# jtag.net
KiCad netlist of a schematic drawn in Altium Designer
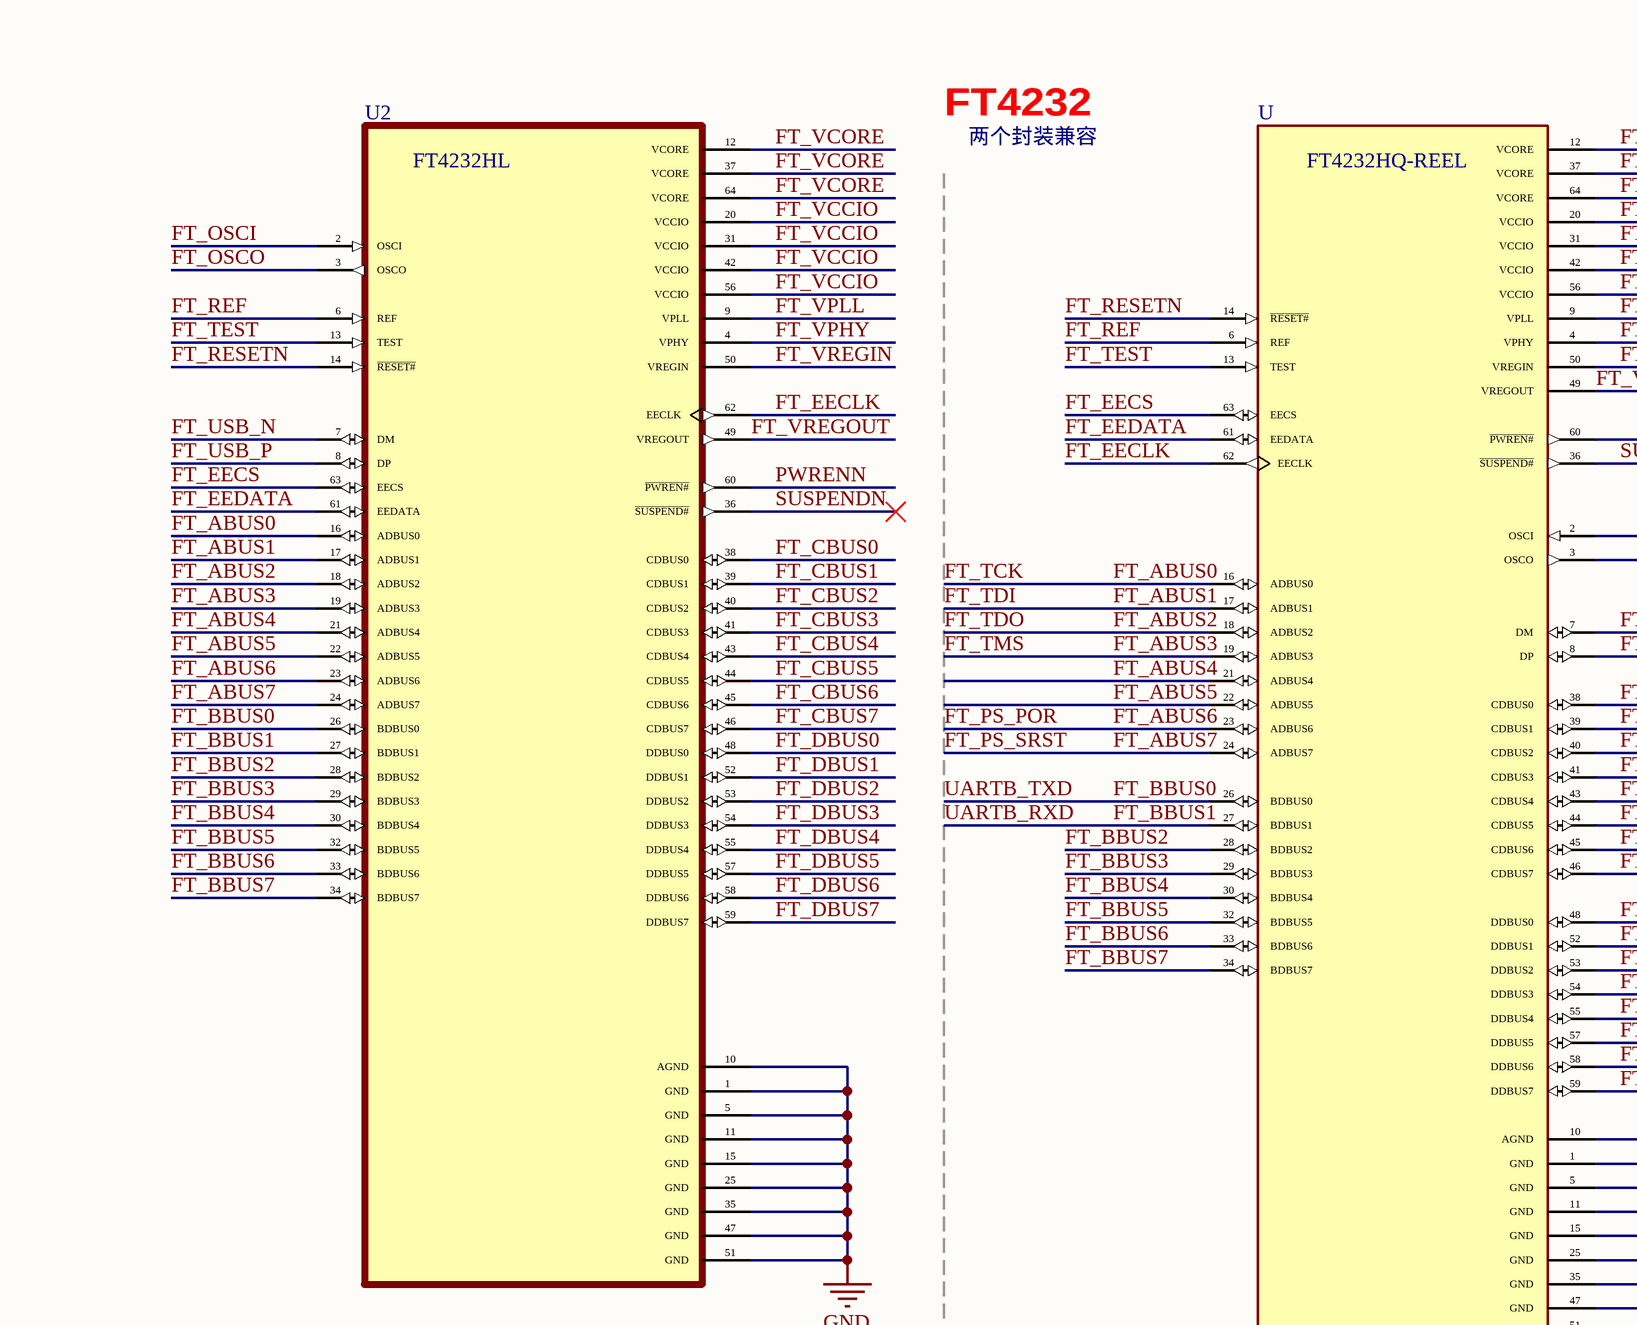
[diagram p0: jtag.schdoc, top left]
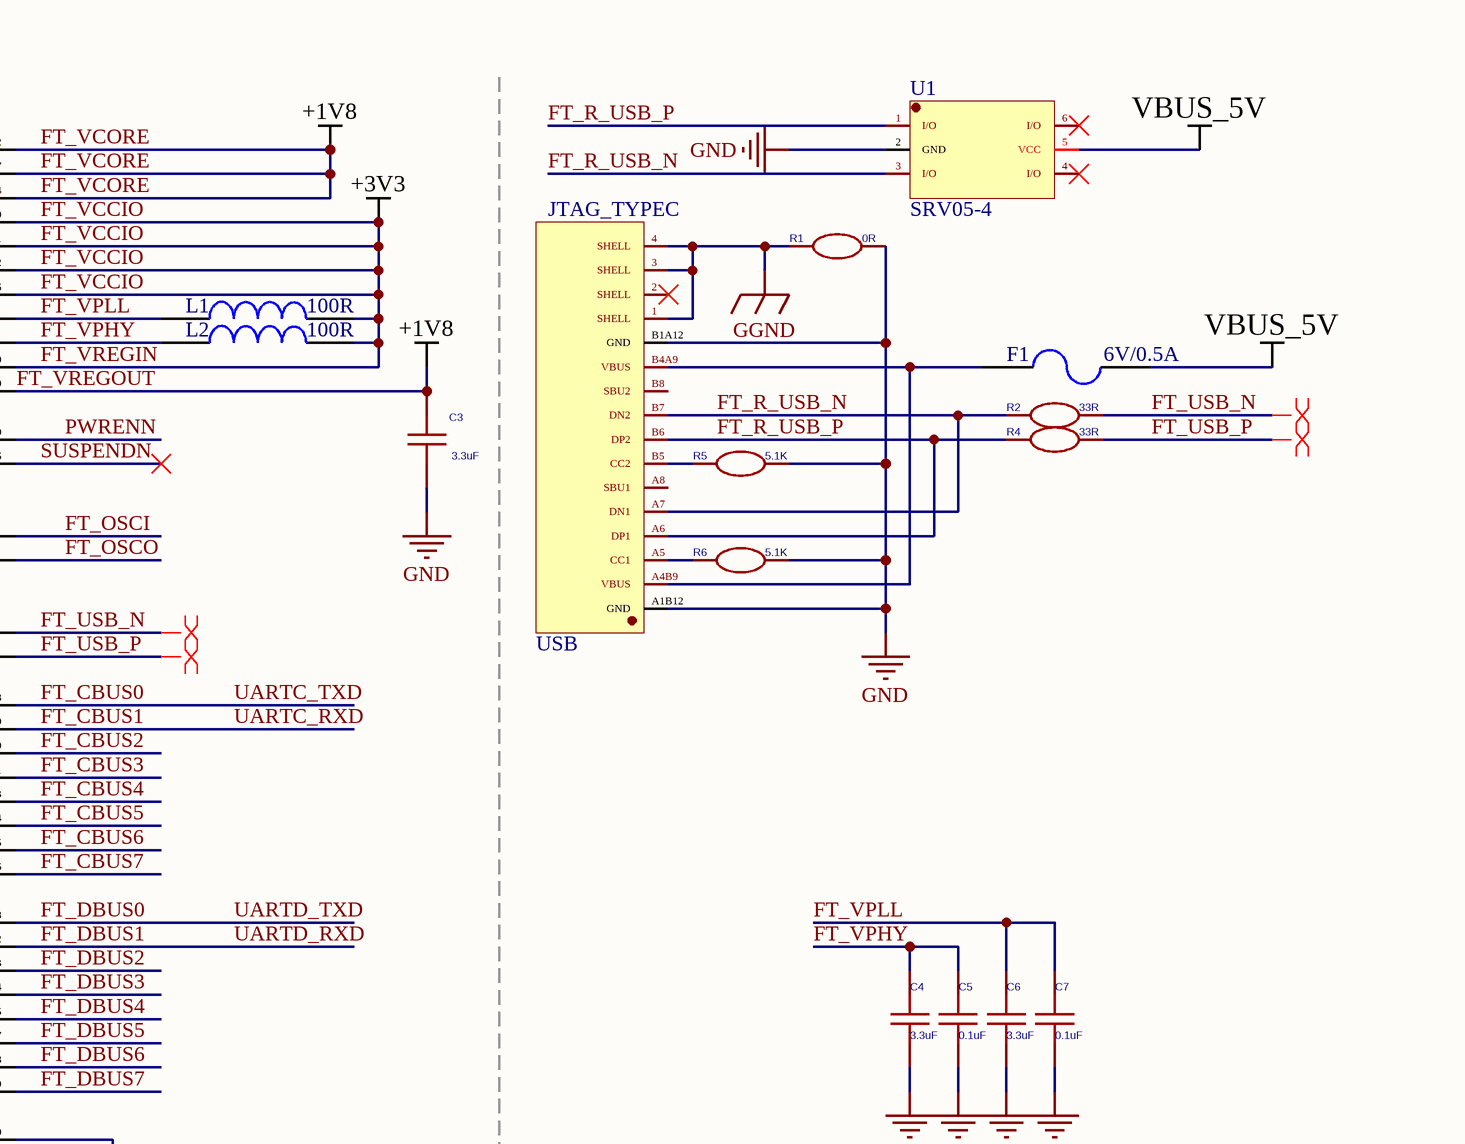
[diagram p1: jtag.schdoc, top right]
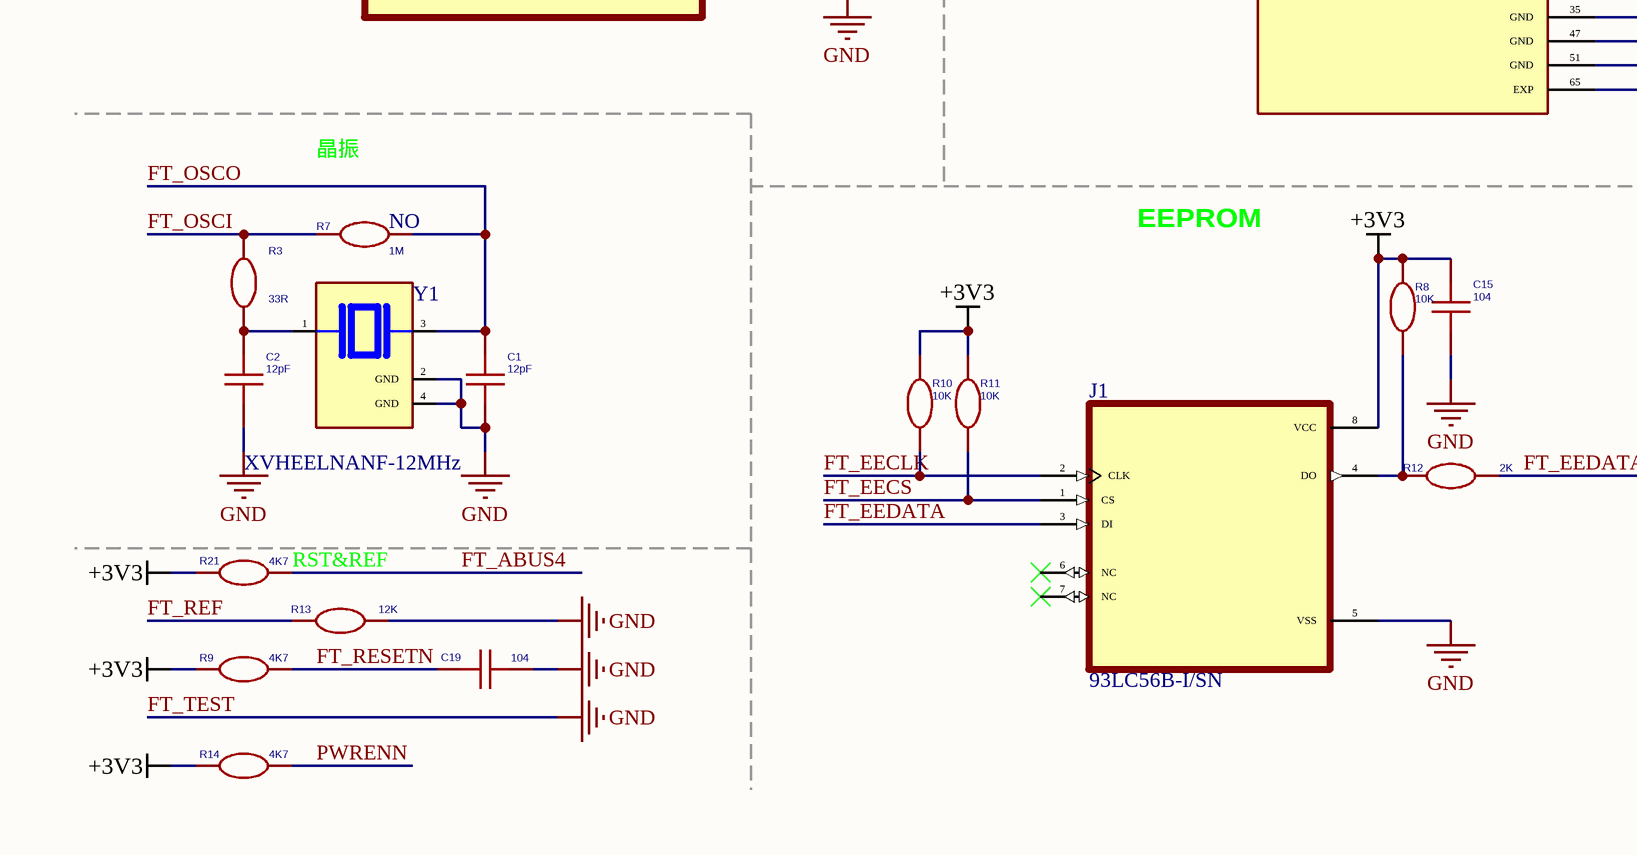
[diagram p2: jtag.schdoc, bottom left]
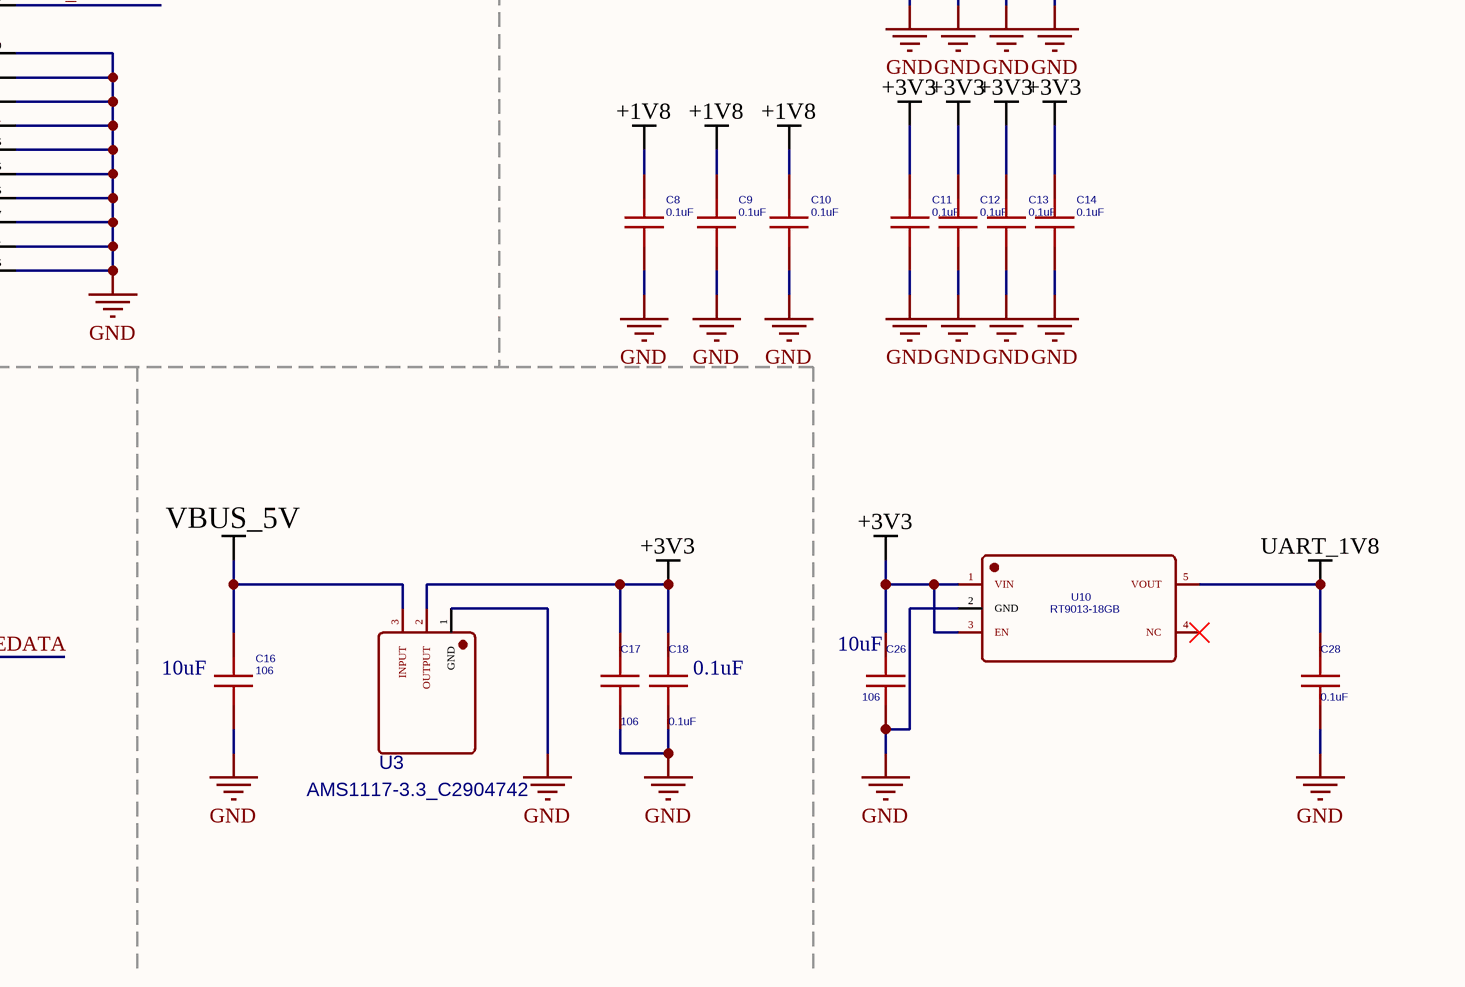
[diagram p3: jtag.schdoc, bottom right]

(export (version "E")
  (design (tool "Eeschema 10.0.6"))
  (components
    (comp (ref "C1")
      (value "12pF")
      (footprint "0603C")
      (fields (field (name "CONTRIBUTOR") "LCEDA_Lib"))
      (libsource (lib "altium-import") (part "root_3_12pF_"))
    )
    (comp (ref "C2")
      (value "12pF")
      (footprint "0603C")
      (fields (field (name "CONTRIBUTOR") "LCEDA_Lib"))
      (libsource (lib "altium-import") (part "root_3_12pF_"))
    )
    (comp (ref "C3")
      (value "3.3uF")
      (footprint "0603C")
      (fields (field (name "CONTRIBUTOR") "LCEDA_Lib"))
      (libsource (lib "altium-import") (part "root_1_104_"))
    )
    (comp (ref "C4")
      (value "3.3uF")
      (footprint "0603C")
      (fields (field (name "CONTRIBUTOR") "LCEDA_Lib"))
      (libsource (lib "altium-import") (part "root_1_104_"))
    )
    (comp (ref "C5")
      (value "0.1uF")
      (footprint "0603C")
      (fields (field (name "CONTRIBUTOR") "LCEDA_Lib"))
      (libsource (lib "altium-import") (part "root_1_104_"))
    )
    (comp (ref "C6")
      (value "3.3uF")
      (footprint "0603C")
      (fields (field (name "CONTRIBUTOR") "LCEDA_Lib"))
      (libsource (lib "altium-import") (part "root_1_104_"))
    )
    (comp (ref "C7")
      (value "0.1uF")
      (footprint "0603C")
      (fields (field (name "CONTRIBUTOR") "LCEDA_Lib"))
      (libsource (lib "altium-import") (part "root_1_104_"))
    )
    (comp (ref "C8")
      (value "0.1uF")
      (footprint "0603C")
      (fields (field (name "CONTRIBUTOR") "LCEDA_Lib"))
      (libsource (lib "altium-import") (part "root_1_104_"))
    )
    (comp (ref "C9")
      (value "0.1uF")
      (footprint "0603C")
      (fields (field (name "CONTRIBUTOR") "LCEDA_Lib"))
      (libsource (lib "altium-import") (part "root_1_104_"))
    )
    (comp (ref "C10")
      (value "0.1uF")
      (footprint "0603C")
      (fields (field (name "CONTRIBUTOR") "LCEDA_Lib"))
      (libsource (lib "altium-import") (part "root_1_104_"))
    )
    (comp (ref "C11")
      (value "0.1uF")
      (footprint "0603C")
      (fields (field (name "CONTRIBUTOR") "LCEDA_Lib"))
      (libsource (lib "altium-import") (part "root_1_104_"))
    )
    (comp (ref "C12")
      (value "0.1uF")
      (footprint "0603C")
      (fields (field (name "CONTRIBUTOR") "LCEDA_Lib"))
      (libsource (lib "altium-import") (part "root_1_104_"))
    )
    (comp (ref "C13")
      (value "0.1uF")
      (footprint "0603C")
      (fields (field (name "CONTRIBUTOR") "LCEDA_Lib"))
      (libsource (lib "altium-import") (part "root_1_104_"))
    )
    (comp (ref "C14")
      (value "0.1uF")
      (footprint "0603C")
      (fields (field (name "CONTRIBUTOR") "LCEDA_Lib"))
      (libsource (lib "altium-import") (part "root_1_104_"))
    )
    (comp (ref "C15")
      (value "104")
      (footprint "0603C")
      (fields (field (name "CONTRIBUTOR") "LCEDA_Lib"))
      (libsource (lib "altium-import") (part "root_1_104_"))
    )
    (comp (ref "C16")
      (value "106")
      (footprint "0603C")
      (fields (field (name "CONTRIBUTOR") "LCEDA_Lib"))
      (libsource (lib "altium-import") (part "root_1_106_"))
    )
    (comp (ref "C17")
      (value "106")
      (footprint "0603C")
      (fields (field (name "CONTRIBUTOR") "LCEDA_Lib"))
      (libsource (lib "altium-import") (part "root_1_106_"))
    )
    (comp (ref "C18")
      (value "0.1uF")
      (footprint "0603C")
      (fields (field (name "CONTRIBUTOR") "LCEDA_Lib"))
      (libsource (lib "altium-import") (part "root_1_104_"))
    )
    (comp (ref "C19")
      (value "104")
      (footprint "0603C")
      (fields (field (name "CONTRIBUTOR") "LCEDA_Lib"))
      (libsource (lib "altium-import") (part "root_0_104_"))
    )
    (comp (ref "C26")
      (value "106")
      (footprint "0603C")
      (fields (field (name "CONTRIBUTOR") "LCEDA_Lib"))
      (libsource (lib "altium-import") (part "root_1_106_"))
    )
    (comp (ref "C28")
      (value "0.1uF")
      (footprint "0603C")
      (fields (field (name "CONTRIBUTOR") "LCEDA_Lib"))
      (libsource (lib "altium-import") (part "root_1_104_"))
    )
    (comp (ref "F1") (value "6V/0.5A") (footprint "FUSE-1812") (libsource (lib "保险丝") (part "FUSE")))
    (comp (ref "J1")
      (value "93LC56B-I/SN")
      (footprint "SOIC127P599X175-8N")
      (description "EEPROM Memory IC 2Kb (128 x 16) SPI 3MHz 8-SOIC")
      (fields (field (name "MF") "Microchip") (field (name "DIGI-KEY_PART_NUMBER") "93LC56B-I/SN15KVAO-ND"))
      (libsource (lib "93LC56B-I_SN") (part "93LC56B-I/SN"))
    )
    (comp (ref "JTAG_TYPEC")
      (value "USB")
      (footprint "USB-C-16PIN")
      (libsource (lib "USB") (part "USB-C-16PIN"))
    )
    (comp (ref "L1")
      (value "100R")
      (footprint "0805L")
      (description "INDUCTOR")
      (libsource (lib "电感") (part "INDUCTOR"))
    )
    (comp (ref "L2")
      (value "100R")
      (footprint "0805L")
      (description "INDUCTOR")
      (libsource (lib "电感") (part "INDUCTOR"))
    )
    (comp (ref "R1")
      (value "0R")
      (footprint "0603R")
      (fields (field (name "CONTRIBUTOR") "LCEDA_Lib"))
      (libsource (lib "altium-import") (part "root_2_10K_"))
    )
    (comp (ref "R2")
      (value "33R")
      (footprint "0603R")
      (fields (field (name "CONTRIBUTOR") "LCEDA_Lib"))
      (libsource (lib "altium-import") (part "root_2_10K_"))
    )
    (comp (ref "R3")
      (value "33R")
      (footprint "0603R")
      (fields (field (name "CONTRIBUTOR") "LCEDA_Lib"))
      (libsource (lib "altium-import") (part "root_1_10K_"))
    )
    (comp (ref "R4")
      (value "33R")
      (footprint "0603R")
      (fields (field (name "CONTRIBUTOR") "LCEDA_Lib"))
      (libsource (lib "altium-import") (part "root_2_10K_"))
    )
    (comp (ref "R5")
      (value "5.1K")
      (footprint "0603R")
      (fields (field (name "CONTRIBUTOR") "LCEDA_Lib"))
      (libsource (lib "altium-import") (part "root_2_10K_"))
    )
    (comp (ref "R6")
      (value "5.1K")
      (footprint "0603R")
      (fields (field (name "CONTRIBUTOR") "LCEDA_Lib"))
      (libsource (lib "altium-import") (part "root_2_10K_"))
    )
    (comp (ref "R7")
      (value "1M")
      (footprint "0603R")
      (fields (field (name "STUFF") "NO") (field (name "CONTRIBUTOR") "LCEDA_Lib"))
      (libsource (lib "altium-import") (part "root_2_10K_"))
    )
    (comp (ref "R8")
      (value "10K")
      (footprint "0603R")
      (fields (field (name "CONTRIBUTOR") "LCEDA_Lib"))
      (libsource (lib "altium-import") (part "root_1_10K_"))
    )
    (comp (ref "R9")
      (value "4K7")
      (footprint "0603R")
      (fields (field (name "CONTRIBUTOR") "LCEDA_Lib"))
      (libsource (lib "altium-import") (part "root_0_4K7_"))
    )
    (comp (ref "R10")
      (value "10K")
      (footprint "0603R")
      (fields (field (name "CONTRIBUTOR") "LCEDA_Lib"))
      (libsource (lib "altium-import") (part "root_1_10K_"))
    )
    (comp (ref "R11")
      (value "10K")
      (footprint "0603R")
      (fields (field (name "CONTRIBUTOR") "LCEDA_Lib"))
      (libsource (lib "altium-import") (part "root_1_10K_"))
    )
    (comp (ref "R12")
      (value "2K")
      (footprint "0603R")
      (fields (field (name "CONTRIBUTOR") "LCEDA_Lib"))
      (libsource (lib "altium-import") (part "root_0_10K_"))
    )
    (comp (ref "R13")
      (value "12K")
      (footprint "0603R")
      (fields (field (name "CONTRIBUTOR") "LCEDA_Lib"))
      (libsource (lib "altium-import") (part "root_0_12K_"))
    )
    (comp (ref "R14")
      (value "4K7")
      (footprint "0603R")
      (fields (field (name "CONTRIBUTOR") "LCEDA_Lib"))
      (libsource (lib "altium-import") (part "root_0_4K7_"))
    )
    (comp (ref "R21")
      (value "4K7")
      (footprint "0603R")
      (fields (field (name "CONTRIBUTOR") "LCEDA_Lib"))
      (libsource (lib "altium-import") (part "root_0_4K7_"))
    )
    (comp (ref "U")
      (value "FT4232HQ-REEL")
      (footprint "QFN50P900X900X105-65N")
      (description "USB Bridge, USB to UART USB 2.0 UART Interface 64-QFN _9x9_")
      (fields (field (name "DIGI-KEY_PART_NUMBER") "768-1027-1-ND") (field (name "MF") "FTDI, Future"))
      (libsource (lib "FT4232HQ-REEL") (part "FT4232HQ-REEL"))
    )
    (comp (ref "U1") (value "SRV05-4") (footprint "SOT23-6") (libsource (lib "未分类IC") (part "SRV05-4")))
    (comp (ref "U2")
      (value "FT4232HL")
      (footprint "QFP50P1200X1200X160-64N")
      (description "USB Hi-Speed to Quad Channel Serial UART/JTAG/SPI/I2C IC - LQFP-64")
      (libsource (lib "FT4232HL") (part "FT4232HL"))
    )
    (comp (ref "U3")
      (value "AMS1117-3.3_C2904742")
      (footprint "SOT-89-3_L4.5-W2.5-P1.50-LS4.1-BL")
      (fields
        (field (name "BOM_SUPPLIER PART") "C2904742")
        (field (name "BOM_MANUFACTURER PART") "AMS1117-3.3")
        (field (name "CONTRIBUTOR") "LCSC")
      )
      (libsource (lib "altium-import") (part "root_3_AMS1117-3.3_C2904742_"))
    )
    (comp (ref "U10")
      (value "RT9013-18GB")
      (footprint "SOT-23-5_L3.0-W1.7-P0.95-LS2.8-BR")
      (fields (field (name "BOM_SUPPLIER PART") "C59969"))
      (libsource (lib "altium-import") (part "root_0_RT9013-18GB_"))
    )
    (comp (ref "Y1")
      (value "XVHEELNANF-12MHz")
      (footprint "XTAL_ABM8G-12.000MHZ-B4Y-T")
      (description "12 MHz Â±30ppm Crystal 10pF 120 Ohms 4-SMD, No Lead")
      (fields (field (name "MP") "ABM8G-12.000MHZ-B4Y-T") (field (name "MF") "Abracon"))
      (libsource (lib "ABM8G-12.000MHZ-B4Y-T") (part "ABM8G-12.000MHZ-B4Y-T"))
    )
  )
  (nets
    (net (code "1") (name "+1V8") (class "Default")
      (node (ref "C10") (pin "2") (pinfunction "2_2") (pintype "passive"))
      (node (ref "C3") (pin "2") (pinfunction "2_2") (pintype "passive"))
      (node (ref "C8") (pin "2") (pinfunction "2_2") (pintype "passive"))
      (node (ref "C9") (pin "2") (pinfunction "2_2") (pintype "passive"))
      (node (ref "U") (pin "12") (pinfunction "VCORE_12") (pintype "power_in"))
      (node (ref "U") (pin "37") (pinfunction "VCORE_37") (pintype "power_in"))
      (node (ref "U") (pin "49") (pinfunction "VREGOUT_49") (pintype "power_in"))
      (node (ref "U") (pin "64") (pinfunction "VCORE_64") (pintype "power_in"))
      (node (ref "U2") (pin "12") (pinfunction "VCORE_12") (pintype "power_in"))
      (node (ref "U2") (pin "37") (pinfunction "VCORE_37") (pintype "power_in"))
      (node (ref "U2") (pin "49") (pinfunction "VREGOUT_49") (pintype "output"))
      (node (ref "U2") (pin "64") (pinfunction "VCORE_64") (pintype "power_in"))
    )
    (net (code "2") (name "+3V3") (class "Default")
      (node (ref "C11") (pin "2") (pinfunction "2_2") (pintype "passive"))
      (node (ref "C12") (pin "2") (pinfunction "2_2") (pintype "passive"))
      (node (ref "C13") (pin "2") (pinfunction "2_2") (pintype "passive"))
      (node (ref "C14") (pin "2") (pinfunction "2_2") (pintype "passive"))
      (node (ref "C15") (pin "2") (pinfunction "2_2") (pintype "passive"))
      (node (ref "C17") (pin "2") (pinfunction "2_2") (pintype "passive"))
      (node (ref "C18") (pin "2") (pinfunction "2_2") (pintype "passive"))
      (node (ref "C26") (pin "2") (pinfunction "2_2") (pintype "passive"))
      (node (ref "J1") (pin "8") (pinfunction "VCC_8") (pintype "power_in"))
      (node (ref "L1") (pin "2") (pinfunction "2_2") (pintype "passive"))
      (node (ref "L2") (pin "2") (pinfunction "2_2") (pintype "passive"))
      (node (ref "R10") (pin "2") (pinfunction "2_2") (pintype "passive"))
      (node (ref "R11") (pin "2") (pinfunction "2_2") (pintype "passive"))
      (node (ref "R14") (pin "1") (pinfunction "1_1") (pintype "passive"))
      (node (ref "R21") (pin "1") (pinfunction "1_1") (pintype "passive"))
      (node (ref "R8") (pin "2") (pinfunction "2_2") (pintype "passive"))
      (node (ref "R9") (pin "1") (pinfunction "1_1") (pintype "passive"))
      (node (ref "U") (pin "20") (pinfunction "VCCIO_20") (pintype "power_in"))
      (node (ref "U") (pin "31") (pinfunction "VCCIO_31") (pintype "power_in"))
      (node (ref "U") (pin "42") (pinfunction "VCCIO_42") (pintype "power_in"))
      (node (ref "U") (pin "50") (pinfunction "VREGIN_50") (pintype "power_in"))
      (node (ref "U") (pin "56") (pinfunction "VCCIO_56") (pintype "power_in"))
      (node (ref "U10") (pin "1") (pinfunction "VIN_1") (pintype "passive"))
      (node (ref "U10") (pin "3") (pinfunction "EN_3") (pintype "passive"))
      (node (ref "U2") (pin "20") (pinfunction "VCCIO_20") (pintype "power_in"))
      (node (ref "U2") (pin "31") (pinfunction "VCCIO_31") (pintype "power_in"))
      (node (ref "U2") (pin "42") (pinfunction "VCCIO_42") (pintype "power_in"))
      (node (ref "U2") (pin "50") (pinfunction "VREGIN_50") (pintype "power_in"))
      (node (ref "U2") (pin "56") (pinfunction "VCCIO_56") (pintype "power_in"))
      (node (ref "U3") (pin "2") (pinfunction "OUTPUT_2") (pintype "passive"))
    )
    (net (code "3") (name "/FT_ABUS0") (class "Default")
      (node (ref "U") (pin "16") (pinfunction "ADBUS0_16") (pintype "bidirectional"))
      (node (ref "U2") (pin "16") (pinfunction "ADBUS0_16") (pintype "bidirectional"))
    )
    (net (code "4") (name "/FT_ABUS1") (class "Default")
      (node (ref "U") (pin "17") (pinfunction "ADBUS1_17") (pintype "bidirectional"))
      (node (ref "U2") (pin "17") (pinfunction "ADBUS1_17") (pintype "bidirectional"))
    )
    (net (code "5") (name "/FT_ABUS2") (class "Default")
      (node (ref "U") (pin "18") (pinfunction "ADBUS2_18") (pintype "bidirectional"))
      (node (ref "U2") (pin "18") (pinfunction "ADBUS2_18") (pintype "bidirectional"))
    )
    (net (code "6") (name "/FT_ABUS3") (class "Default")
      (node (ref "U") (pin "19") (pinfunction "ADBUS3_19") (pintype "bidirectional"))
      (node (ref "U2") (pin "19") (pinfunction "ADBUS3_19") (pintype "bidirectional"))
    )
    (net (code "7") (name "/FT_ABUS4") (class "Default")
      (node (ref "R21") (pin "2") (pinfunction "2_2") (pintype "passive"))
      (node (ref "U") (pin "21") (pinfunction "ADBUS4_21") (pintype "bidirectional"))
      (node (ref "U2") (pin "21") (pinfunction "ADBUS4_21") (pintype "bidirectional"))
    )
    (net (code "8") (name "/FT_ABUS5") (class "Default")
      (node (ref "U") (pin "22") (pinfunction "ADBUS5_22") (pintype "bidirectional"))
      (node (ref "U2") (pin "22") (pinfunction "ADBUS5_22") (pintype "bidirectional"))
    )
    (net (code "9") (name "/FT_ABUS6") (class "Default")
      (node (ref "U") (pin "23") (pinfunction "ADBUS6_23") (pintype "bidirectional"))
      (node (ref "U2") (pin "23") (pinfunction "ADBUS6_23") (pintype "bidirectional"))
    )
    (net (code "10") (name "/FT_ABUS7") (class "Default")
      (node (ref "U") (pin "24") (pinfunction "ADBUS7_24") (pintype "bidirectional"))
      (node (ref "U2") (pin "24") (pinfunction "ADBUS7_24") (pintype "bidirectional"))
    )
    (net (code "11") (name "/FT_BBUS0") (class "Default")
      (node (ref "U") (pin "26") (pinfunction "BDBUS0_26") (pintype "bidirectional"))
      (node (ref "U2") (pin "26") (pinfunction "BDBUS0_26") (pintype "bidirectional"))
    )
    (net (code "12") (name "/FT_BBUS1") (class "Default")
      (node (ref "U") (pin "27") (pinfunction "BDBUS1_27") (pintype "bidirectional"))
      (node (ref "U2") (pin "27") (pinfunction "BDBUS1_27") (pintype "bidirectional"))
    )
    (net (code "13") (name "/FT_BBUS2") (class "Default")
      (node (ref "U") (pin "28") (pinfunction "BDBUS2_28") (pintype "bidirectional"))
      (node (ref "U2") (pin "28") (pinfunction "BDBUS2_28") (pintype "bidirectional"))
    )
    (net (code "14") (name "/FT_BBUS3") (class "Default")
      (node (ref "U") (pin "29") (pinfunction "BDBUS3_29") (pintype "bidirectional"))
      (node (ref "U2") (pin "29") (pinfunction "BDBUS3_29") (pintype "bidirectional"))
    )
    (net (code "15") (name "/FT_BBUS4") (class "Default")
      (node (ref "U") (pin "30") (pinfunction "BDBUS4_30") (pintype "bidirectional"))
      (node (ref "U2") (pin "30") (pinfunction "BDBUS4_30") (pintype "bidirectional"))
    )
    (net (code "16") (name "/FT_BBUS5") (class "Default")
      (node (ref "U") (pin "32") (pinfunction "BDBUS5_32") (pintype "bidirectional"))
      (node (ref "U2") (pin "32") (pinfunction "BDBUS5_32") (pintype "bidirectional"))
    )
    (net (code "17") (name "/FT_BBUS6") (class "Default")
      (node (ref "U") (pin "33") (pinfunction "BDBUS6_33") (pintype "bidirectional"))
      (node (ref "U2") (pin "33") (pinfunction "BDBUS6_33") (pintype "bidirectional"))
    )
    (net (code "18") (name "/FT_BBUS7") (class "Default")
      (node (ref "U") (pin "34") (pinfunction "BDBUS7_34") (pintype "bidirectional"))
      (node (ref "U2") (pin "34") (pinfunction "BDBUS7_34") (pintype "bidirectional"))
    )
    (net (code "19") (name "/FT_CBUS0") (class "Default")
      (node (ref "U") (pin "38") (pinfunction "CDBUS0_38") (pintype "bidirectional"))
      (node (ref "U2") (pin "38") (pinfunction "CDBUS0_38") (pintype "bidirectional"))
    )
    (net (code "20") (name "/FT_CBUS1") (class "Default")
      (node (ref "U") (pin "39") (pinfunction "CDBUS1_39") (pintype "bidirectional"))
      (node (ref "U2") (pin "39") (pinfunction "CDBUS1_39") (pintype "bidirectional"))
    )
    (net (code "21") (name "/FT_CBUS2") (class "Default")
      (node (ref "U") (pin "40") (pinfunction "CDBUS2_40") (pintype "bidirectional"))
      (node (ref "U2") (pin "40") (pinfunction "CDBUS2_40") (pintype "bidirectional"))
    )
    (net (code "22") (name "/FT_CBUS3") (class "Default")
      (node (ref "U") (pin "41") (pinfunction "CDBUS3_41") (pintype "bidirectional"))
      (node (ref "U2") (pin "41") (pinfunction "CDBUS3_41") (pintype "bidirectional"))
    )
    (net (code "23") (name "/FT_CBUS4") (class "Default")
      (node (ref "U") (pin "43") (pinfunction "CDBUS4_43") (pintype "bidirectional"))
      (node (ref "U2") (pin "43") (pinfunction "CDBUS4_43") (pintype "bidirectional"))
    )
    (net (code "24") (name "/FT_CBUS5") (class "Default")
      (node (ref "U") (pin "44") (pinfunction "CDBUS5_44") (pintype "bidirectional"))
      (node (ref "U2") (pin "44") (pinfunction "CDBUS5_44") (pintype "bidirectional"))
    )
    (net (code "25") (name "/FT_CBUS6") (class "Default")
      (node (ref "U") (pin "45") (pinfunction "CDBUS6_45") (pintype "bidirectional"))
      (node (ref "U2") (pin "45") (pinfunction "CDBUS6_45") (pintype "bidirectional"))
    )
    (net (code "26") (name "/FT_CBUS7") (class "Default")
      (node (ref "U") (pin "46") (pinfunction "CDBUS7_46") (pintype "bidirectional"))
      (node (ref "U2") (pin "46") (pinfunction "CDBUS7_46") (pintype "bidirectional"))
    )
    (net (code "27") (name "/FT_DBUS0") (class "Default")
      (node (ref "U") (pin "48") (pinfunction "DDBUS0_48") (pintype "bidirectional"))
      (node (ref "U2") (pin "48") (pinfunction "DDBUS0_48") (pintype "bidirectional"))
    )
    (net (code "28") (name "/FT_DBUS1") (class "Default")
      (node (ref "U") (pin "52") (pinfunction "DDBUS1_52") (pintype "bidirectional"))
      (node (ref "U2") (pin "52") (pinfunction "DDBUS1_52") (pintype "bidirectional"))
    )
    (net (code "29") (name "/FT_DBUS2") (class "Default")
      (node (ref "U") (pin "53") (pinfunction "DDBUS2_53") (pintype "bidirectional"))
      (node (ref "U2") (pin "53") (pinfunction "DDBUS2_53") (pintype "bidirectional"))
    )
    (net (code "30") (name "/FT_DBUS3") (class "Default")
      (node (ref "U") (pin "54") (pinfunction "DDBUS3_54") (pintype "bidirectional"))
      (node (ref "U2") (pin "54") (pinfunction "DDBUS3_54") (pintype "bidirectional"))
    )
    (net (code "31") (name "/FT_DBUS4") (class "Default")
      (node (ref "U") (pin "55") (pinfunction "DDBUS4_55") (pintype "bidirectional"))
      (node (ref "U2") (pin "55") (pinfunction "DDBUS4_55") (pintype "bidirectional"))
    )
    (net (code "32") (name "/FT_DBUS5") (class "Default")
      (node (ref "U") (pin "57") (pinfunction "DDBUS5_57") (pintype "bidirectional"))
      (node (ref "U2") (pin "57") (pinfunction "DDBUS5_57") (pintype "bidirectional"))
    )
    (net (code "33") (name "/FT_DBUS6") (class "Default")
      (node (ref "U") (pin "58") (pinfunction "DDBUS6_58") (pintype "bidirectional"))
      (node (ref "U2") (pin "58") (pinfunction "DDBUS6_58") (pintype "bidirectional"))
    )
    (net (code "34") (name "/FT_DBUS7") (class "Default")
      (node (ref "U") (pin "59") (pinfunction "DDBUS7_59") (pintype "bidirectional"))
      (node (ref "U2") (pin "59") (pinfunction "DDBUS7_59") (pintype "bidirectional"))
    )
    (net (code "35") (name "/FT_EECLK") (class "Default")
      (node (ref "J1") (pin "2") (pinfunction "CLK_2") (pintype "input"))
      (node (ref "R10") (pin "1") (pinfunction "1_1") (pintype "passive"))
      (node (ref "U") (pin "62") (pinfunction "EECLK_62") (pintype "output"))
      (node (ref "U2") (pin "62") (pinfunction "EECLK_62") (pintype "output"))
    )
    (net (code "36") (name "/FT_EECS") (class "Default")
      (node (ref "J1") (pin "1") (pinfunction "CS_1") (pintype "input"))
      (node (ref "R11") (pin "1") (pinfunction "1_1") (pintype "passive"))
      (node (ref "U") (pin "63") (pinfunction "EECS_63") (pintype "bidirectional"))
      (node (ref "U2") (pin "63") (pinfunction "EECS_63") (pintype "bidirectional"))
    )
    (net (code "37") (name "/FT_EEDATA") (class "Default")
      (node (ref "J1") (pin "3") (pinfunction "DI_3") (pintype "input"))
      (node (ref "R12") (pin "2") (pinfunction "2_2") (pintype "passive"))
      (node (ref "U") (pin "61") (pinfunction "EEDATA_61") (pintype "bidirectional"))
      (node (ref "U2") (pin "61") (pinfunction "EEDATA_61") (pintype "bidirectional"))
    )
    (net (code "38") (name "/FT_OSCI") (class "Default")
      (node (ref "R3") (pin "2") (pinfunction "2_2") (pintype "passive"))
      (node (ref "R7") (pin "2") (pinfunction "2_2") (pintype "passive"))
      (node (ref "U") (pin "2") (pinfunction "OSCI_2") (pintype "input"))
      (node (ref "U2") (pin "2") (pinfunction "OSCI_2") (pintype "input"))
    )
    (net (code "39") (name "/FT_OSCO") (class "Default")
      (node (ref "C1") (pin "1") (pinfunction "1_1") (pintype "passive"))
      (node (ref "R7") (pin "1") (pinfunction "1_1") (pintype "passive"))
      (node (ref "U") (pin "3") (pinfunction "OSCO_3") (pintype "output"))
      (node (ref "U2") (pin "3") (pinfunction "OSCO_3") (pintype "output"))
      (node (ref "Y1") (pin "3") (pinfunction "2_3") (pintype "passive"))
    )
    (net (code "40") (name "/FT_REF") (class "Default")
      (node (ref "R13") (pin "1") (pinfunction "1_1") (pintype "passive"))
      (node (ref "U") (pin "6") (pinfunction "REF_6") (pintype "input"))
      (node (ref "U2") (pin "6") (pinfunction "REF_6") (pintype "input"))
    )
    (net (code "41") (name "/FT_RESETN") (class "Default")
      (node (ref "C19") (pin "1") (pinfunction "1_1") (pintype "passive"))
      (node (ref "R9") (pin "2") (pinfunction "2_2") (pintype "passive"))
      (node (ref "U") (pin "14") (pinfunction "~{RESET#}_14") (pintype "input"))
      (node (ref "U2") (pin "14") (pinfunction "~{RESET#}_14") (pintype "input"))
    )
    (net (code "42") (name "/FT_R_USB_N") (class "Default")
      (node (ref "JTAG_TYPEC") (pin "A7") (pinfunction "DN1_A7") (pintype "passive"))
      (node (ref "JTAG_TYPEC") (pin "B7") (pinfunction "DN2_B7") (pintype "passive"))
      (node (ref "R2") (pin "2") (pinfunction "2_2") (pintype "passive"))
      (node (ref "U1") (pin "3") (pinfunction "I/O_3") (pintype "passive"))
    )
    (net (code "43") (name "/FT_R_USB_P") (class "Default")
      (node (ref "JTAG_TYPEC") (pin "A6") (pinfunction "DP1_A6") (pintype "passive"))
      (node (ref "JTAG_TYPEC") (pin "B6") (pinfunction "DP2_B6") (pintype "passive"))
      (node (ref "R4") (pin "2") (pinfunction "2_2") (pintype "passive"))
      (node (ref "U1") (pin "1") (pinfunction "I/O_1") (pintype "passive"))
    )
    (net (code "44") (name "/FT_USB_N") (class "Default")
      (node (ref "R2") (pin "1") (pinfunction "1_1") (pintype "passive"))
      (node (ref "U") (pin "7") (pinfunction "DM_7") (pintype "bidirectional"))
      (node (ref "U2") (pin "7") (pinfunction "DM_7") (pintype "bidirectional"))
    )
    (net (code "45") (name "/FT_USB_P") (class "Default")
      (node (ref "R4") (pin "1") (pinfunction "1_1") (pintype "passive"))
      (node (ref "U") (pin "8") (pinfunction "DP_8") (pintype "bidirectional"))
      (node (ref "U2") (pin "8") (pinfunction "DP_8") (pintype "bidirectional"))
    )
    (net (code "46") (name "/FT_VPHY") (class "Default")
      (node (ref "C4") (pin "2") (pinfunction "2_2") (pintype "passive"))
      (node (ref "C5") (pin "2") (pinfunction "2_2") (pintype "passive"))
      (node (ref "L2") (pin "1") (pinfunction "1_1") (pintype "passive"))
      (node (ref "U") (pin "4") (pinfunction "VPHY_4") (pintype "power_in"))
      (node (ref "U2") (pin "4") (pinfunction "VPHY_4") (pintype "power_in"))
    )
    (net (code "47") (name "/FT_VPLL") (class "Default")
      (node (ref "C6") (pin "2") (pinfunction "2_2") (pintype "passive"))
      (node (ref "C7") (pin "2") (pinfunction "2_2") (pintype "passive"))
      (node (ref "L1") (pin "1") (pinfunction "1_1") (pintype "passive"))
      (node (ref "U") (pin "9") (pinfunction "VPLL_9") (pintype "power_in"))
      (node (ref "U2") (pin "9") (pinfunction "VPLL_9") (pintype "power_in"))
    )
    (net (code "48") (name "/PWRENN") (class "Default")
      (node (ref "R14") (pin "2") (pinfunction "2_2") (pintype "passive"))
      (node (ref "U") (pin "60") (pinfunction "~{PWREN#}_60") (pintype "output"))
      (node (ref "U2") (pin "60") (pinfunction "~{PWREN#}_60") (pintype "output"))
    )
    (net (code "49") (name "/SUSPENDN") (class "Default")
      (node (ref "U") (pin "36") (pinfunction "~{SUSPEND#}_36") (pintype "output"))
      (node (ref "U2") (pin "36") (pinfunction "~{SUSPEND#}_36") (pintype "output"))
    )
    (net (code "50") (name "GGND") (class "Default")
      (node (ref "JTAG_TYPEC") (pin "1") (pinfunction "SHELL_1") (pintype "passive"))
      (node (ref "JTAG_TYPEC") (pin "3") (pinfunction "SHELL_3") (pintype "passive"))
      (node (ref "JTAG_TYPEC") (pin "4") (pinfunction "SHELL_4") (pintype "passive"))
      (node (ref "R1") (pin "2") (pinfunction "2_2") (pintype "passive"))
    )
    (net (code "51") (name "GND") (class "Default")
      (node (ref "C1") (pin "2") (pinfunction "2_2") (pintype "passive"))
      (node (ref "C10") (pin "1") (pinfunction "1_1") (pintype "passive"))
      (node (ref "C11") (pin "1") (pinfunction "1_1") (pintype "passive"))
      (node (ref "C12") (pin "1") (pinfunction "1_1") (pintype "passive"))
      (node (ref "C13") (pin "1") (pinfunction "1_1") (pintype "passive"))
      (node (ref "C14") (pin "1") (pinfunction "1_1") (pintype "passive"))
      (node (ref "C15") (pin "1") (pinfunction "1_1") (pintype "passive"))
      (node (ref "C16") (pin "1") (pinfunction "1_1") (pintype "passive"))
      (node (ref "C17") (pin "1") (pinfunction "1_1") (pintype "passive"))
      (node (ref "C18") (pin "1") (pinfunction "1_1") (pintype "passive"))
      (node (ref "C19") (pin "2") (pinfunction "2_2") (pintype "passive"))
      (node (ref "C2") (pin "2") (pinfunction "2_2") (pintype "passive"))
      (node (ref "C26") (pin "1") (pinfunction "1_1") (pintype "passive"))
      (node (ref "C28") (pin "1") (pinfunction "1_1") (pintype "passive"))
      (node (ref "C3") (pin "1") (pinfunction "1_1") (pintype "passive"))
      (node (ref "C4") (pin "1") (pinfunction "1_1") (pintype "passive"))
      (node (ref "C5") (pin "1") (pinfunction "1_1") (pintype "passive"))
      (node (ref "C6") (pin "1") (pinfunction "1_1") (pintype "passive"))
      (node (ref "C7") (pin "1") (pinfunction "1_1") (pintype "passive"))
      (node (ref "C8") (pin "1") (pinfunction "1_1") (pintype "passive"))
      (node (ref "C9") (pin "1") (pinfunction "1_1") (pintype "passive"))
      (node (ref "J1") (pin "5") (pinfunction "VSS_5") (pintype "power_in"))
      (node (ref "JTAG_TYPEC") (pin "A1B12") (pinfunction "GND_A1B12") (pintype "passive"))
      (node (ref "JTAG_TYPEC") (pin "B1A12") (pinfunction "GND_B1A12") (pintype "passive"))
      (node (ref "R1") (pin "1") (pinfunction "1_1") (pintype "passive"))
      (node (ref "R13") (pin "2") (pinfunction "2_2") (pintype "passive"))
      (node (ref "R5") (pin "1") (pinfunction "1_1") (pintype "passive"))
      (node (ref "R6") (pin "1") (pinfunction "1_1") (pintype "passive"))
      (node (ref "U") (pin "1") (pinfunction "GND_1") (pintype "power_in"))
      (node (ref "U") (pin "10") (pinfunction "AGND_10") (pintype "power_in"))
      (node (ref "U") (pin "11") (pinfunction "GND_11") (pintype "power_in"))
      (node (ref "U") (pin "13") (pinfunction "TEST_13") (pintype "input"))
      (node (ref "U") (pin "15") (pinfunction "GND_15") (pintype "power_in"))
      (node (ref "U") (pin "25") (pinfunction "GND_25") (pintype "power_in"))
      (node (ref "U") (pin "35") (pinfunction "GND_35") (pintype "power_in"))
      (node (ref "U") (pin "47") (pinfunction "GND_47") (pintype "power_in"))
      (node (ref "U") (pin "5") (pinfunction "GND_5") (pintype "power_in"))
      (node (ref "U") (pin "51") (pinfunction "GND_51") (pintype "power_in"))
      (node (ref "U") (pin "65") (pinfunction "EXP_65") (pintype "power_in"))
      (node (ref "U1") (pin "2") (pinfunction "GND_2") (pintype "passive"))
      (node (ref "U10") (pin "2") (pinfunction "GND_2") (pintype "passive"))
      (node (ref "U2") (pin "1") (pinfunction "GND_1") (pintype "power_in"))
      (node (ref "U2") (pin "10") (pinfunction "AGND_10") (pintype "power_in"))
      (node (ref "U2") (pin "11") (pinfunction "GND_11") (pintype "power_in"))
      (node (ref "U2") (pin "13") (pinfunction "TEST_13") (pintype "input"))
      (node (ref "U2") (pin "15") (pinfunction "GND_15") (pintype "power_in"))
      (node (ref "U2") (pin "25") (pinfunction "GND_25") (pintype "power_in"))
      (node (ref "U2") (pin "35") (pinfunction "GND_35") (pintype "power_in"))
      (node (ref "U2") (pin "47") (pinfunction "GND_47") (pintype "power_in"))
      (node (ref "U2") (pin "5") (pinfunction "GND_5") (pintype "power_in"))
      (node (ref "U2") (pin "51") (pinfunction "GND_51") (pintype "power_in"))
      (node (ref "U3") (pin "1") (pinfunction "GND_1") (pintype "passive"))
      (node (ref "Y1") (pin "2") (pinfunction "GND_2") (pintype "power_in"))
      (node (ref "Y1") (pin "4") (pinfunction "GND_4") (pintype "power_in"))
    )
    (net (code "52") (name "Net-(C2-Pad1)") (class "Default")
      (node (ref "C2") (pin "1") (pinfunction "1_1") (pintype "passive"))
      (node (ref "R3") (pin "1") (pinfunction "1_1") (pintype "passive"))
      (node (ref "Y1") (pin "1") (pinfunction "1_1") (pintype "passive"))
    )
    (net (code "53") (name "Net-(F1-Pad1)") (class "Default")
      (node (ref "F1") (pin "1") (pinfunction "1_1") (pintype "passive"))
      (node (ref "JTAG_TYPEC") (pin "A4B9") (pinfunction "VBUS_A4B9") (pintype "passive"))
      (node (ref "JTAG_TYPEC") (pin "B4A9") (pinfunction "VBUS_B4A9") (pintype "passive"))
    )
    (net (code "54") (name "Net-(J1-DO)") (class "Default")
      (node (ref "J1") (pin "4") (pinfunction "DO_4") (pintype "output"))
      (node (ref "R12") (pin "1") (pinfunction "1_1") (pintype "passive"))
      (node (ref "R8") (pin "1") (pinfunction "1_1") (pintype "passive"))
    )
    (net (code "55") (name "Net-(JTAG_TYPEC-CC1)") (class "Default")
      (node (ref "JTAG_TYPEC") (pin "A5") (pinfunction "CC1_A5") (pintype "passive"))
      (node (ref "R6") (pin "2") (pinfunction "2_2") (pintype "passive"))
    )
    (net (code "56") (name "Net-(JTAG_TYPEC-CC2)") (class "Default")
      (node (ref "JTAG_TYPEC") (pin "B5") (pinfunction "CC2_B5") (pintype "passive"))
      (node (ref "R5") (pin "2") (pinfunction "2_2") (pintype "passive"))
    )
    (net (code "57") (name "UART_1V8") (class "Default")
      (node (ref "C28") (pin "2") (pinfunction "2_2") (pintype "passive"))
      (node (ref "U10") (pin "5") (pinfunction "VOUT_5") (pintype "passive"))
    )
    (net (code "58") (name "VBUS_5V") (class "Default")
      (node (ref "C16") (pin "2") (pinfunction "2_2") (pintype "passive"))
      (node (ref "F1") (pin "2") (pinfunction "2_2") (pintype "passive"))
      (node (ref "U1") (pin "5") (pinfunction "VCC_5") (pintype "passive"))
      (node (ref "U3") (pin "3") (pinfunction "INPUT_3") (pintype "passive"))
    )
    (net (code "59") (name "unconnected-(J1-NC-Pad6)") (class "Default")
      (node (ref "J1") (pin "6") (pinfunction "NC_6") (pintype "bidirectional+no_connect"))
    )
    (net (code "60") (name "unconnected-(J1-NC-Pad7)") (class "Default")
      (node (ref "J1") (pin "7") (pinfunction "NC_7") (pintype "bidirectional+no_connect"))
    )
    (net (code "61") (name "unconnected-(JTAG_TYPEC-SBU1-PadA8)") (class "Default")
      (node (ref "JTAG_TYPEC") (pin "A8") (pinfunction "SBU1_A8") (pintype "passive"))
    )
    (net (code "62") (name "unconnected-(JTAG_TYPEC-SBU2-PadB8)") (class "Default")
      (node (ref "JTAG_TYPEC") (pin "B8") (pinfunction "SBU2_B8") (pintype "passive"))
    )
    (net (code "63") (name "unconnected-(JTAG_TYPEC-SHELL-Pad2)") (class "Default")
      (node (ref "JTAG_TYPEC") (pin "2") (pinfunction "SHELL_2") (pintype "passive+no_connect"))
    )
    (net (code "64") (name "unconnected-(U1-I{slash}O-Pad4)") (class "Default")
      (node (ref "U1") (pin "4") (pinfunction "I/O_4") (pintype "passive+no_connect"))
    )
    (net (code "65") (name "unconnected-(U1-I{slash}O-Pad6)") (class "Default")
      (node (ref "U1") (pin "6") (pinfunction "I/O_6") (pintype "passive+no_connect"))
    )
    (net (code "66") (name "unconnected-(U10-NC-Pad4)") (class "Default")
      (node (ref "U10") (pin "4") (pinfunction "NC_4") (pintype "passive+no_connect"))
    )
  )
)
